# Pro_Trinket-Micro_Keyboard_Jr_v1.net
KiCad netlist of a schematic drawn in EAGLE
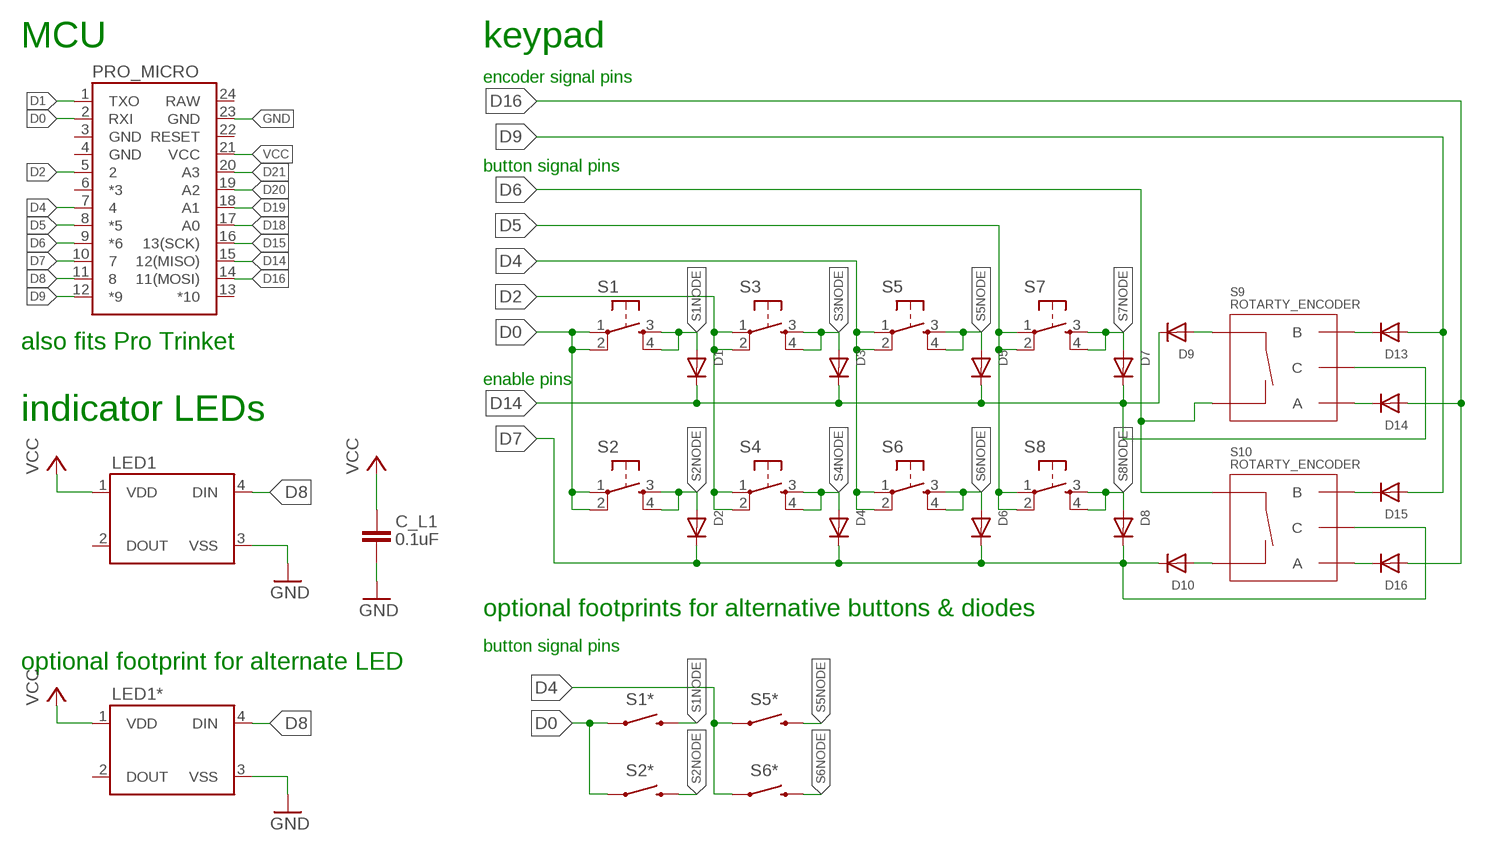
[diagram p0: schematic, sheet 1]

(export (version "E")
  (design (tool "Eeschema 10.0.6"))
  (components
    (comp (ref "C_L1")
      (value "0.1uF")
      (footprint "eagle-import:0603-CAP")
      (libsource (lib "eagle-import") (part "22PF-50V-5%(0603)"))
    )
    (comp (ref "D1")
      (value "DIODESOD-123")
      (footprint "eagle-import:SOD-123")
      (libsource (lib "eagle-import") (part "DIODESOD-123"))
    )
    (comp (ref "D2")
      (value "DIODESOD-123")
      (footprint "eagle-import:SOD-123")
      (libsource (lib "eagle-import") (part "DIODESOD-123"))
    )
    (comp (ref "D3")
      (value "DIODESOD-123")
      (footprint "eagle-import:SOD-123")
      (libsource (lib "eagle-import") (part "DIODESOD-123"))
    )
    (comp (ref "D4")
      (value "DIODESOD-123")
      (footprint "eagle-import:SOD-123")
      (libsource (lib "eagle-import") (part "DIODESOD-123"))
    )
    (comp (ref "D5")
      (value "DIODESOD-123")
      (footprint "eagle-import:SOD-123")
      (libsource (lib "eagle-import") (part "DIODESOD-123"))
    )
    (comp (ref "D6")
      (value "DIODESOD-123")
      (footprint "eagle-import:SOD-123")
      (libsource (lib "eagle-import") (part "DIODESOD-123"))
    )
    (comp (ref "D7")
      (value "DIODESOD-123")
      (footprint "eagle-import:SOD-123")
      (libsource (lib "eagle-import") (part "DIODESOD-123"))
    )
    (comp (ref "D8")
      (value "DIODESOD-123")
      (footprint "eagle-import:SOD-123")
      (libsource (lib "eagle-import") (part "DIODESOD-123"))
    )
    (comp (ref "D9")
      (value "DIODESOD-123")
      (footprint "eagle-import:SOD-123")
      (libsource (lib "eagle-import") (part "DIODESOD-123"))
    )
    (comp (ref "D10")
      (value "DIODESOD-123")
      (footprint "eagle-import:SOD-123")
      (libsource (lib "eagle-import") (part "DIODESOD-123"))
    )
    (comp (ref "D13")
      (value "DIODESOD-123")
      (footprint "eagle-import:SOD-123")
      (libsource (lib "eagle-import") (part "DIODESOD-123"))
    )
    (comp (ref "D14")
      (value "DIODESOD-123")
      (footprint "eagle-import:SOD-123")
      (libsource (lib "eagle-import") (part "DIODESOD-123"))
    )
    (comp (ref "D15")
      (value "DIODESOD-123")
      (footprint "eagle-import:SOD-123")
      (libsource (lib "eagle-import") (part "DIODESOD-123"))
    )
    (comp (ref "D16")
      (value "DIODESOD-123")
      (footprint "eagle-import:SOD-123")
      (libsource (lib "eagle-import") (part "DIODESOD-123"))
    )
    (comp (ref "LED1")
      (value "WS2812B")
      (footprint "eagle-import:WS2812B")
      (libsource (lib "eagle-import") (part "WS2812B"))
    )
    (comp (ref "LED1*")
      (value "WS2812B")
      (footprint "eagle-import:WS2812B")
      (libsource (lib "eagle-import") (part "WS2812B"))
    )
    (comp (ref "PRO_MICRO")
      (value "ARDUINO_PRO_MICRO")
      (footprint "eagle-import:ARDUINO_PRO_MICRO")
      (libsource (lib "eagle-import") (part "ARDUINO_PRO_MICRO"))
    )
    (comp (ref "S1")
      (value "TACTILE-SWITCH-PTH")
      (footprint "eagle-import:TAC-SWITCH-PTH")
      (libsource (lib "eagle-import") (part "TACTILE-SWITCH-PTH"))
    )
    (comp (ref "S1*")
      (value "SWITCH-MOMENTARY-212MM")
      (footprint "eagle-import:TACTILE-PTH-12MM")
      (libsource (lib "eagle-import") (part "SWITCH-MOMENTARY-212MM"))
    )
    (comp (ref "S2")
      (value "TACTILE-SWITCH-PTH")
      (footprint "eagle-import:TAC-SWITCH-PTH")
      (libsource (lib "eagle-import") (part "TACTILE-SWITCH-PTH"))
    )
    (comp (ref "S2*")
      (value "SWITCH-MOMENTARY-212MM")
      (footprint "eagle-import:TACTILE-PTH-12MM")
      (libsource (lib "eagle-import") (part "SWITCH-MOMENTARY-212MM"))
    )
    (comp (ref "S3")
      (value "TACTILE-SWITCH-PTH")
      (footprint "eagle-import:TAC-SWITCH-PTH")
      (libsource (lib "eagle-import") (part "TACTILE-SWITCH-PTH"))
    )
    (comp (ref "S4")
      (value "TACTILE-SWITCH-PTH")
      (footprint "eagle-import:TAC-SWITCH-PTH")
      (libsource (lib "eagle-import") (part "TACTILE-SWITCH-PTH"))
    )
    (comp (ref "S5")
      (value "TACTILE-SWITCH-PTH")
      (footprint "eagle-import:TAC-SWITCH-PTH")
      (libsource (lib "eagle-import") (part "TACTILE-SWITCH-PTH"))
    )
    (comp (ref "S5*")
      (value "SWITCH-MOMENTARY-212MM")
      (footprint "eagle-import:TACTILE-PTH-12MM")
      (libsource (lib "eagle-import") (part "SWITCH-MOMENTARY-212MM"))
    )
    (comp (ref "S6")
      (value "TACTILE-SWITCH-PTH")
      (footprint "eagle-import:TAC-SWITCH-PTH")
      (libsource (lib "eagle-import") (part "TACTILE-SWITCH-PTH"))
    )
    (comp (ref "S6*")
      (value "SWITCH-MOMENTARY-212MM")
      (footprint "eagle-import:TACTILE-PTH-12MM")
      (libsource (lib "eagle-import") (part "SWITCH-MOMENTARY-212MM"))
    )
    (comp (ref "S7")
      (value "TACTILE-SWITCH-PTH")
      (footprint "eagle-import:TAC-SWITCH-PTH")
      (libsource (lib "eagle-import") (part "TACTILE-SWITCH-PTH"))
    )
    (comp (ref "S8")
      (value "TACTILE-SWITCH-PTH")
      (footprint "eagle-import:TAC-SWITCH-PTH")
      (libsource (lib "eagle-import") (part "TACTILE-SWITCH-PTH"))
    )
    (comp (ref "S9")
      (value "ROTARTY_ENCODER")
      (footprint "eagle-import:ROTARY_ENC_PLAIN")
      (libsource (lib "eagle-import") (part "ROTARTY_ENCODER"))
    )
    (comp (ref "S10")
      (value "ROTARTY_ENCODER")
      (footprint "eagle-import:ROTARY_ENC_PLAIN")
      (libsource (lib "eagle-import") (part "ROTARTY_ENCODER"))
    )
  )
  (nets
    (net (code "1") (name "D0") (class "Default")
      (node (ref "PRO_MICRO") (pin "2") (pinfunction "RXI_2") (pintype "bidirectional"))
      (node (ref "S1") (pin "1") (pinfunction "1_1") (pintype "passive"))
      (node (ref "S1") (pin "2") (pinfunction "2_2") (pintype "passive"))
      (node (ref "S1*") (pin "1") (pinfunction "1_1") (pintype "passive"))
      (node (ref "S1*") (pin "2") (pinfunction "1_2") (pintype "passive"))
      (node (ref "S2") (pin "1") (pinfunction "1_1") (pintype "passive"))
      (node (ref "S2") (pin "2") (pinfunction "2_2") (pintype "passive"))
      (node (ref "S2*") (pin "1") (pinfunction "1_1") (pintype "passive"))
      (node (ref "S2*") (pin "2") (pinfunction "1_2") (pintype "passive"))
    )
    (net (code "2") (name "D1") (class "Default")
      (node (ref "PRO_MICRO") (pin "1") (pinfunction "TXO_1") (pintype "bidirectional"))
    )
    (net (code "3") (name "D2") (class "Default")
      (node (ref "PRO_MICRO") (pin "5") (pinfunction "2_5") (pintype "bidirectional"))
      (node (ref "S3") (pin "1") (pinfunction "1_1") (pintype "passive"))
      (node (ref "S3") (pin "2") (pinfunction "2_2") (pintype "passive"))
      (node (ref "S4") (pin "1") (pinfunction "1_1") (pintype "passive"))
      (node (ref "S4") (pin "2") (pinfunction "2_2") (pintype "passive"))
    )
    (net (code "4") (name "D4") (class "Default")
      (node (ref "PRO_MICRO") (pin "7") (pinfunction "4_7") (pintype "bidirectional"))
      (node (ref "S5") (pin "1") (pinfunction "1_1") (pintype "passive"))
      (node (ref "S5") (pin "2") (pinfunction "2_2") (pintype "passive"))
      (node (ref "S5*") (pin "1") (pinfunction "1_1") (pintype "passive"))
      (node (ref "S5*") (pin "2") (pinfunction "1_2") (pintype "passive"))
      (node (ref "S6") (pin "1") (pinfunction "1_1") (pintype "passive"))
      (node (ref "S6") (pin "2") (pinfunction "2_2") (pintype "passive"))
      (node (ref "S6*") (pin "1") (pinfunction "1_1") (pintype "passive"))
      (node (ref "S6*") (pin "2") (pinfunction "1_2") (pintype "passive"))
    )
    (net (code "5") (name "D5") (class "Default")
      (node (ref "PRO_MICRO") (pin "8") (pinfunction "*5_8") (pintype "bidirectional"))
      (node (ref "S7") (pin "1") (pinfunction "1_1") (pintype "passive"))
      (node (ref "S7") (pin "2") (pinfunction "2_2") (pintype "passive"))
      (node (ref "S8") (pin "1") (pinfunction "1_1") (pintype "passive"))
      (node (ref "S8") (pin "2") (pinfunction "2_2") (pintype "passive"))
    )
    (net (code "6") (name "D6") (class "Default")
      (node (ref "PRO_MICRO") (pin "9") (pinfunction "*6_9") (pintype "bidirectional"))
      (node (ref "S10") (pin "SW+") (pinfunction "SW+_SW+") (pintype "bidirectional"))
      (node (ref "S9") (pin "SW-") (pinfunction "SW-_SW-") (pintype "bidirectional"))
    )
    (net (code "7") (name "D7") (class "Default")
      (node (ref "D10") (pin "C") (pinfunction "C_C") (pintype "passive"))
      (node (ref "D2") (pin "C") (pinfunction "C_C") (pintype "passive"))
      (node (ref "D4") (pin "C") (pinfunction "C_C") (pintype "passive"))
      (node (ref "D6") (pin "C") (pinfunction "C_C") (pintype "passive"))
      (node (ref "D8") (pin "C") (pinfunction "C_C") (pintype "passive"))
      (node (ref "PRO_MICRO") (pin "10") (pinfunction "7_10") (pintype "bidirectional"))
      (node (ref "S10") (pin "C") (pinfunction "C_C") (pintype "bidirectional"))
    )
    (net (code "8") (name "D8") (class "Default")
      (node (ref "LED1") (pin "4") (pinfunction "DIN_4") (pintype "input"))
      (node (ref "LED1*") (pin "4") (pinfunction "DIN_4") (pintype "input"))
      (node (ref "PRO_MICRO") (pin "11") (pinfunction "8_11") (pintype "bidirectional"))
    )
    (net (code "9") (name "D9") (class "Default")
      (node (ref "D13") (pin "A") (pinfunction "A_A") (pintype "passive"))
      (node (ref "D15") (pin "A") (pinfunction "A_A") (pintype "passive"))
      (node (ref "PRO_MICRO") (pin "12") (pinfunction "*9_12") (pintype "bidirectional"))
    )
    (net (code "10") (name "D14") (class "Default")
      (node (ref "D1") (pin "C") (pinfunction "C_C") (pintype "passive"))
      (node (ref "D3") (pin "C") (pinfunction "C_C") (pintype "passive"))
      (node (ref "D5") (pin "C") (pinfunction "C_C") (pintype "passive"))
      (node (ref "D7") (pin "C") (pinfunction "C_C") (pintype "passive"))
      (node (ref "D9") (pin "C") (pinfunction "C_C") (pintype "passive"))
      (node (ref "PRO_MICRO") (pin "15") (pinfunction "12(MISO)_15") (pintype "bidirectional"))
      (node (ref "S9") (pin "C") (pinfunction "C_C") (pintype "bidirectional"))
    )
    (net (code "11") (name "D15") (class "Default")
      (node (ref "PRO_MICRO") (pin "16") (pinfunction "13(SCK)_16") (pintype "bidirectional"))
    )
    (net (code "12") (name "D16") (class "Default")
      (node (ref "D14") (pin "A") (pinfunction "A_A") (pintype "passive"))
      (node (ref "D16") (pin "A") (pinfunction "A_A") (pintype "passive"))
      (node (ref "PRO_MICRO") (pin "14") (pinfunction "11(MOSI)_14") (pintype "bidirectional"))
    )
    (net (code "13") (name "D18") (class "Default")
      (node (ref "PRO_MICRO") (pin "17") (pinfunction "A0_17") (pintype "bidirectional"))
    )
    (net (code "14") (name "D19") (class "Default")
      (node (ref "PRO_MICRO") (pin "18") (pinfunction "A1_18") (pintype "bidirectional"))
    )
    (net (code "15") (name "D20") (class "Default")
      (node (ref "PRO_MICRO") (pin "19") (pinfunction "A2_19") (pintype "bidirectional"))
    )
    (net (code "16") (name "D21") (class "Default")
      (node (ref "PRO_MICRO") (pin "20") (pinfunction "A3_20") (pintype "bidirectional"))
    )
    (net (code "17") (name "GND") (class "Default")
      (node (ref "C_L1") (pin "1") (pinfunction "1_1") (pintype "passive"))
      (node (ref "LED1") (pin "3") (pinfunction "VSS_3") (pintype "power_in"))
      (node (ref "LED1*") (pin "3") (pinfunction "VSS_3") (pintype "power_in"))
      (node (ref "PRO_MICRO") (pin "23") (pinfunction "GND_23") (pintype "bidirectional"))
    )
    (net (code "18") (name "Net-(D9-PadA)") (class "Default")
      (node (ref "D9") (pin "A") (pinfunction "A_A") (pintype "passive"))
      (node (ref "S9") (pin "SW+") (pinfunction "SW+_SW+") (pintype "bidirectional"))
    )
    (net (code "19") (name "Net-(D10-PadA)") (class "Default")
      (node (ref "D10") (pin "A") (pinfunction "A_A") (pintype "passive"))
      (node (ref "S10") (pin "SW-") (pinfunction "SW-_SW-") (pintype "bidirectional"))
    )
    (net (code "20") (name "Net-(D13-PadC)") (class "Default")
      (node (ref "D13") (pin "C") (pinfunction "C_C") (pintype "passive"))
      (node (ref "S9") (pin "B") (pinfunction "B_B") (pintype "bidirectional"))
    )
    (net (code "21") (name "Net-(D14-PadC)") (class "Default")
      (node (ref "D14") (pin "C") (pinfunction "C_C") (pintype "passive"))
      (node (ref "S9") (pin "A") (pinfunction "A_A") (pintype "bidirectional"))
    )
    (net (code "22") (name "Net-(D15-PadC)") (class "Default")
      (node (ref "D15") (pin "C") (pinfunction "C_C") (pintype "passive"))
      (node (ref "S10") (pin "B") (pinfunction "B_B") (pintype "bidirectional"))
    )
    (net (code "23") (name "Net-(D16-PadC)") (class "Default")
      (node (ref "D16") (pin "C") (pinfunction "C_C") (pintype "passive"))
      (node (ref "S10") (pin "A") (pinfunction "A_A") (pintype "bidirectional"))
    )
    (net (code "24") (name "S1NODE") (class "Default")
      (node (ref "D1") (pin "A") (pinfunction "A_A") (pintype "passive"))
      (node (ref "S1") (pin "3") (pinfunction "3_3") (pintype "passive"))
      (node (ref "S1") (pin "4") (pinfunction "4_4") (pintype "passive"))
      (node (ref "S1*") (pin "3") (pinfunction "2_3") (pintype "passive"))
      (node (ref "S1*") (pin "4") (pinfunction "2_4") (pintype "passive"))
    )
    (net (code "25") (name "S2NODE") (class "Default")
      (node (ref "D2") (pin "A") (pinfunction "A_A") (pintype "passive"))
      (node (ref "S2") (pin "3") (pinfunction "3_3") (pintype "passive"))
      (node (ref "S2") (pin "4") (pinfunction "4_4") (pintype "passive"))
      (node (ref "S2*") (pin "3") (pinfunction "2_3") (pintype "passive"))
      (node (ref "S2*") (pin "4") (pinfunction "2_4") (pintype "passive"))
    )
    (net (code "26") (name "S3NODE") (class "Default")
      (node (ref "D3") (pin "A") (pinfunction "A_A") (pintype "passive"))
      (node (ref "S3") (pin "3") (pinfunction "3_3") (pintype "passive"))
      (node (ref "S3") (pin "4") (pinfunction "4_4") (pintype "passive"))
    )
    (net (code "27") (name "S4NODE") (class "Default")
      (node (ref "D4") (pin "A") (pinfunction "A_A") (pintype "passive"))
      (node (ref "S4") (pin "3") (pinfunction "3_3") (pintype "passive"))
      (node (ref "S4") (pin "4") (pinfunction "4_4") (pintype "passive"))
    )
    (net (code "28") (name "S5NODE") (class "Default")
      (node (ref "D5") (pin "A") (pinfunction "A_A") (pintype "passive"))
      (node (ref "S5") (pin "3") (pinfunction "3_3") (pintype "passive"))
      (node (ref "S5") (pin "4") (pinfunction "4_4") (pintype "passive"))
      (node (ref "S5*") (pin "3") (pinfunction "2_3") (pintype "passive"))
      (node (ref "S5*") (pin "4") (pinfunction "2_4") (pintype "passive"))
    )
    (net (code "29") (name "S6NODE") (class "Default")
      (node (ref "D6") (pin "A") (pinfunction "A_A") (pintype "passive"))
      (node (ref "S6") (pin "3") (pinfunction "3_3") (pintype "passive"))
      (node (ref "S6") (pin "4") (pinfunction "4_4") (pintype "passive"))
      (node (ref "S6*") (pin "3") (pinfunction "2_3") (pintype "passive"))
      (node (ref "S6*") (pin "4") (pinfunction "2_4") (pintype "passive"))
    )
    (net (code "30") (name "S7NODE") (class "Default")
      (node (ref "D7") (pin "A") (pinfunction "A_A") (pintype "passive"))
      (node (ref "S7") (pin "3") (pinfunction "3_3") (pintype "passive"))
      (node (ref "S7") (pin "4") (pinfunction "4_4") (pintype "passive"))
    )
    (net (code "31") (name "S8NODE") (class "Default")
      (node (ref "D8") (pin "A") (pinfunction "A_A") (pintype "passive"))
      (node (ref "S8") (pin "3") (pinfunction "3_3") (pintype "passive"))
      (node (ref "S8") (pin "4") (pinfunction "4_4") (pintype "passive"))
    )
    (net (code "32") (name "VCC") (class "Default")
      (node (ref "C_L1") (pin "2") (pinfunction "2_2") (pintype "passive"))
      (node (ref "LED1") (pin "1") (pinfunction "VDD_1") (pintype "power_in"))
      (node (ref "LED1*") (pin "1") (pinfunction "VDD_1") (pintype "power_in"))
      (node (ref "PRO_MICRO") (pin "21") (pinfunction "VCC_21") (pintype "bidirectional"))
    )
    (net (code "33") (name "unconnected-(LED1*-DOUT-Pad2)") (class "Default")
      (node (ref "LED1*") (pin "2") (pinfunction "DOUT_2") (pintype "output"))
    )
    (net (code "34") (name "unconnected-(LED1-DOUT-Pad2)") (class "Default")
      (node (ref "LED1") (pin "2") (pinfunction "DOUT_2") (pintype "output"))
    )
    (net (code "35") (name "unconnected-(PRO_MICRO-*3-Pad6)") (class "Default")
      (node (ref "PRO_MICRO") (pin "6") (pinfunction "*3_6") (pintype "bidirectional"))
    )
    (net (code "36") (name "unconnected-(PRO_MICRO-*10-Pad13)") (class "Default")
      (node (ref "PRO_MICRO") (pin "13") (pinfunction "*10_13") (pintype "bidirectional"))
    )
    (net (code "37") (name "unconnected-(PRO_MICRO-GND-Pad3)") (class "Default")
      (node (ref "PRO_MICRO") (pin "3") (pinfunction "GND_3") (pintype "bidirectional"))
    )
    (net (code "38") (name "unconnected-(PRO_MICRO-GND-Pad4)") (class "Default")
      (node (ref "PRO_MICRO") (pin "4") (pinfunction "GND_4") (pintype "bidirectional"))
    )
    (net (code "39") (name "unconnected-(PRO_MICRO-RAW-Pad24)") (class "Default")
      (node (ref "PRO_MICRO") (pin "24") (pinfunction "RAW_24") (pintype "bidirectional"))
    )
    (net (code "40") (name "unconnected-(PRO_MICRO-RESET-Pad22)") (class "Default")
      (node (ref "PRO_MICRO") (pin "22") (pinfunction "RESET_22") (pintype "bidirectional"))
    )
  )
)
